# design.net
KiCad netlist of a schematic drawn in Altium Designer
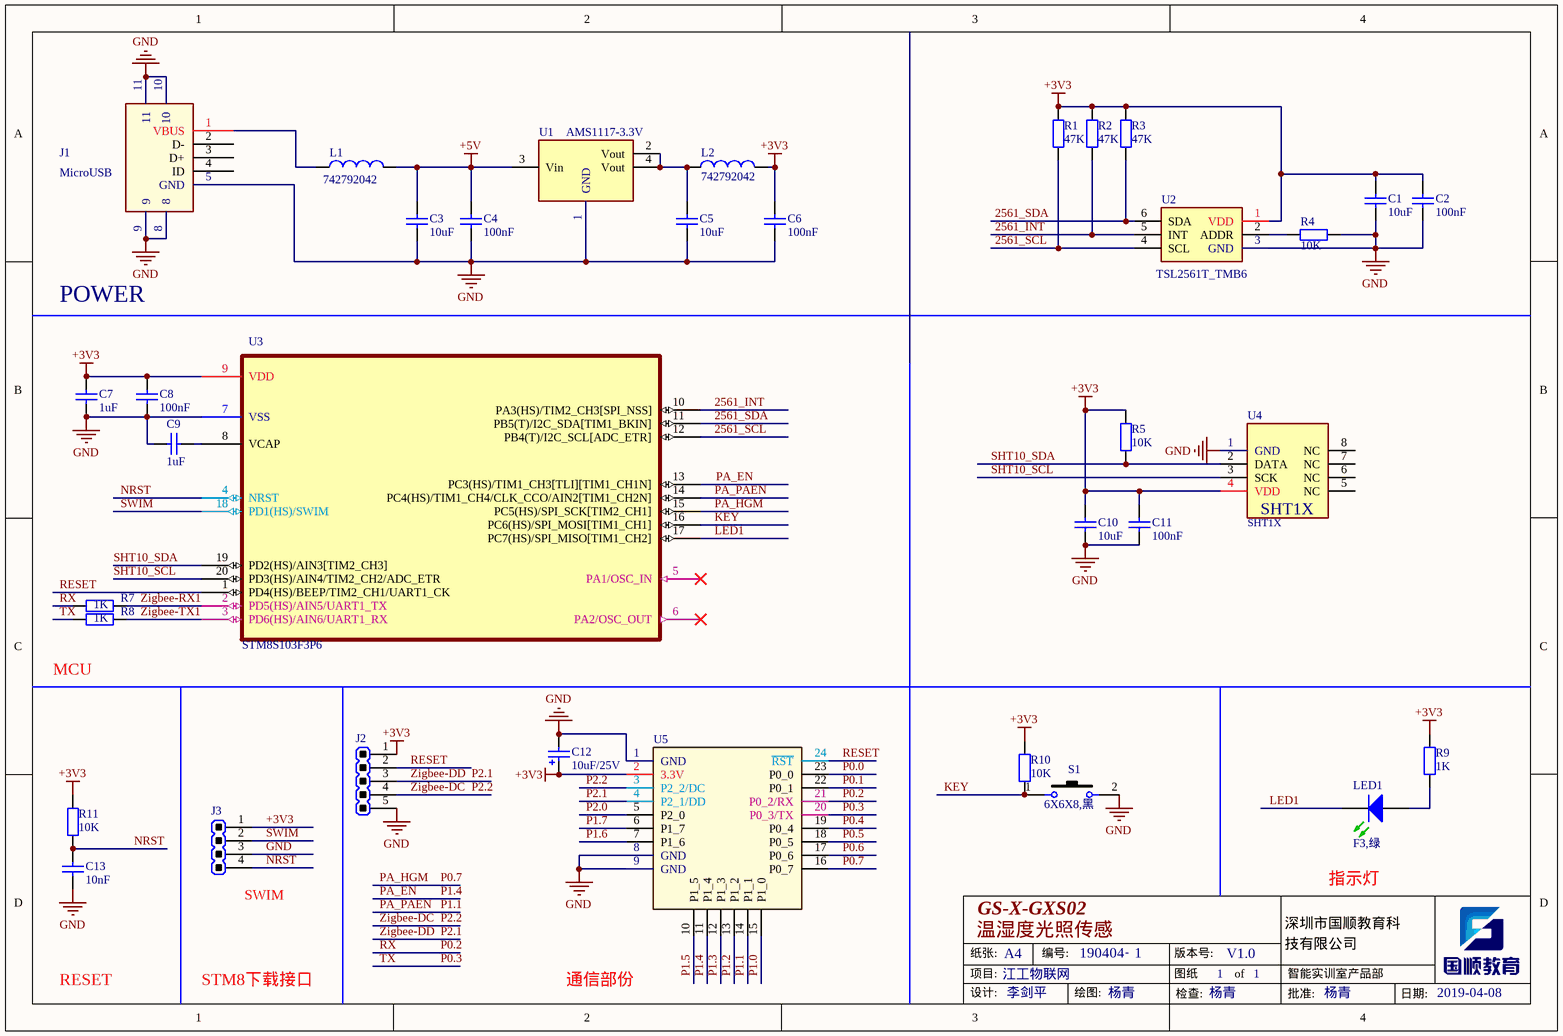
[diagram p0: 温湿度光照传感.SchDoc]

(export (version "E")
  (design (tool "Eeschema 10.0.6"))
  (components
    (comp (ref "C1")
      (value "10uF")
      (footprint "C0603")
      (description "Capacitor")
      (libsource (lib "贴片电容") (part "10uF_16V_0603"))
    )
    (comp (ref "C2")
      (value "100nF")
      (footprint "C0603")
      (description "Capacitor")
      (libsource (lib "贴片电容") (part "100nF_50V_0603"))
    )
    (comp (ref "C3")
      (value "10uF")
      (footprint "C0603")
      (description "Capacitor")
      (libsource (lib "贴片电容") (part "10uF_16V_0603"))
    )
    (comp (ref "C4")
      (value "100nF")
      (footprint "C0603")
      (description "Capacitor")
      (libsource (lib "贴片电容") (part "100nF_50V_0603"))
    )
    (comp (ref "C5")
      (value "10uF")
      (footprint "C0603")
      (description "Capacitor")
      (libsource (lib "贴片电容") (part "10uF_16V_0603"))
    )
    (comp (ref "C6")
      (value "100nF")
      (footprint "C0603")
      (description "Capacitor")
      (libsource (lib "贴片电容") (part "100nF_50V_0603"))
    )
    (comp (ref "C7")
      (value "1uF")
      (footprint "C0603")
      (description "Capacitor")
      (libsource (lib "贴片电容") (part "1uF_25V_X7R_0603"))
    )
    (comp (ref "C8")
      (value "100nF")
      (footprint "C0603")
      (description "Capacitor")
      (libsource (lib "贴片电容") (part "100nF_50V_0603"))
    )
    (comp (ref "C9")
      (value "1uF")
      (footprint "C0603")
      (description "Capacitor")
      (libsource (lib "贴片电容") (part "1uF_25V_X7R_0603"))
    )
    (comp (ref "C10")
      (value "10uF")
      (footprint "C0603")
      (description "Capacitor")
      (libsource (lib "贴片电容") (part "10uF_16V_0603"))
    )
    (comp (ref "C11")
      (value "100nF")
      (footprint "C0603")
      (description "Capacitor")
      (libsource (lib "贴片电容") (part "100nF_50V_0603"))
    )
    (comp (ref "C12")
      (value "10uF/25V")
      (footprint "TC3528X21B")
      (description "钽电容,10uF/25V-3528B")
      (libsource (lib "贴片电容") (part "CAPC-10uF/25V_3528B"))
    )
    (comp (ref "C13")
      (value "10nF")
      (footprint "C0603")
      (description "Capacitor")
      (libsource (lib "贴片电容") (part "10nF_16V_0603"))
    )
    (comp (ref "J1")
      (value "MicroUSB")
      (footprint "USB-F-Micro5P")
      (description "MicroUSB 母座")
      (libsource (lib "接口") (part "USB-F-Miro5P"))
    )
    (comp (ref "J2")
      (value "HDRM-2.54/11-1*5P-AK")
      (footprint "HDRM-2.54-1*5P-AK")
      (description "排针,直")
      (libsource (lib "接口") (part "HDRM-2.54/11-1*5P-AK"))
    )
    (comp (ref "J3")
      (value "HDRM-2.54/11-1*4P-AK")
      (footprint "HDRM-2.54-1*4P-AK")
      (description "排针,直")
      (libsource (lib "接口") (part "HDRM-2.54/11-1*4P-AK"))
    )
    (comp (ref "L1")
      (value "742792042")
      (footprint "L0805")
      (description "WE-CBF,600@100M,500Ohm,200mA,0805,742792042")
      (libsource (lib "电感") (part "BEAD-742792042_0805"))
    )
    (comp (ref "L2")
      (value "742792042")
      (footprint "L0805")
      (description "WE-CBF,600@100M,500Ohm,200mA,0805,742792042")
      (libsource (lib "电感") (part "BEAD-742792042_0805"))
    )
    (comp (ref "LED1")
      (value "F3,绿")
      (footprint "LED-F3-G-H")
      (description "F3,圆头,绿发绿")
      (libsource (lib "二极管") (part "LED-绿_F3"))
    )
    (comp (ref "R1")
      (value "47K")
      (footprint "R0603")
      (description "47K,±5%,0603")
      (libsource (lib "贴片电阻") (part "47K_5%_0603"))
    )
    (comp (ref "R2")
      (value "47K")
      (footprint "R0603")
      (description "47K,±5%,0603")
      (libsource (lib "贴片电阻") (part "47K_5%_0603"))
    )
    (comp (ref "R3")
      (value "47K")
      (footprint "R0603")
      (description "47K,±5%,0603")
      (libsource (lib "贴片电阻") (part "47K_5%_0603"))
    )
    (comp (ref "R4")
      (value "10K")
      (footprint "R0603")
      (description "10K,±5%,0603")
      (libsource (lib "") (part "10K_5%_0603_1"))
    )
    (comp (ref "R5")
      (value "10K")
      (footprint "R0603")
      (description "10K,±5%,0603")
      (libsource (lib "贴片电阻") (part "10K_5%_0603"))
    )
    (comp (ref "R7")
      (value "1K")
      (footprint "R0603")
      (description "1K,±5%,0603")
      (libsource (lib "贴片电阻") (part "1K_5%_0603"))
    )
    (comp (ref "R8")
      (value "1K")
      (footprint "R0603")
      (description "1K,±5%,0603")
      (libsource (lib "贴片电阻") (part "1K_5%_0603"))
    )
    (comp (ref "R9")
      (value "1K")
      (footprint "R0603")
      (description "1K,±5%,0603")
      (libsource (lib "") (part "1K_5%_0603_1"))
    )
    (comp (ref "R10")
      (value "10K")
      (footprint "R0603")
      (description "10K,±5%,0603")
      (libsource (lib "贴片电阻") (part "10K_5%_0603"))
    )
    (comp (ref "R11")
      (value "10K")
      (footprint "R0603")
      (description "10K,±5%,0603")
      (libsource (lib "贴片电阻") (part "10K_5%_0603"))
    )
    (comp (ref "S1")
      (value "6X6X8,黑")
      (footprint "SW-6.0X6.0X8.0-STAND-BK")
      (description "6X6X8,黑,插针,支架")
      (libsource (lib "按键开关") (part "SW-PB_6X6X8-STAND-BK"))
    )
    (comp (ref "U1")
      (value "AMS1117-3.3V")
      (footprint "SOT-223")
      (description "三端稳压器")
      (libsource (lib "IC") (part "AMS1117-3.3V_SOT223"))
    )
    (comp (ref "U2")
      (value "TSL2561T_TMB6")
      (footprint "TSL2561T")
      (description "光照传感器")
      (libsource (lib "传感器") (part "TSL2561T_TMB6"))
    )
    (comp (ref "U3")
      (value "STM8S103F3P6")
      (footprint "TSSOP20-0.65/4.4")
      (description "STM8 ARM-based 32-bit MCU with 8 Kbytes Flash, 20-pin TSSOP, Industrial Temperature")
      (libsource (lib "IC") (part "STM8S103F3P6_TSSOP20"))
    )
    (comp (ref "U4")
      (value "SHT1X")
      (footprint "SHT1X")
      (description "温湿度传感器")
      (libsource (lib "传感器") (part "SHT1X"))
    )
    (comp (ref "U5")
      (value "ZigBee_Z-0003")
      (footprint "Module_ZigBee_Z-0003")
      (description "zigbee模块接口")
      (libsource (lib "其他") (part "Module_ZigBee_Z-0003_1"))
    )
  )
  (nets
    (net (code "1") (name "+3V3") (class "Default")
      (node (ref "C1") (pin "1") (pinfunction "1_1") (pintype "passive"))
      (node (ref "C10") (pin "1") (pinfunction "1_1") (pintype "passive"))
      (node (ref "C11") (pin "1") (pinfunction "1_1") (pintype "passive"))
      (node (ref "C12") (pin "1") (pinfunction "1_1") (pintype "passive"))
      (node (ref "C2") (pin "1") (pinfunction "1_1") (pintype "passive"))
      (node (ref "C6") (pin "1") (pinfunction "1_1") (pintype "passive"))
      (node (ref "C7") (pin "1") (pinfunction "1_1") (pintype "passive"))
      (node (ref "C8") (pin "2") (pinfunction "2_2") (pintype "passive"))
      (node (ref "J2") (pin "1") (pinfunction "1_1") (pintype "passive"))
      (node (ref "J3") (pin "1") (pinfunction "1_1") (pintype "passive"))
      (node (ref "L2") (pin "2") (pinfunction "2_2") (pintype "passive"))
      (node (ref "R1") (pin "2") (pinfunction "2_2") (pintype "passive"))
      (node (ref "R10") (pin "2") (pinfunction "2_2") (pintype "passive"))
      (node (ref "R11") (pin "2") (pinfunction "2_2") (pintype "passive"))
      (node (ref "R2") (pin "2") (pinfunction "2_2") (pintype "passive"))
      (node (ref "R3") (pin "2") (pinfunction "2_2") (pintype "passive"))
      (node (ref "R5") (pin "2") (pinfunction "2_2") (pintype "passive"))
      (node (ref "R9") (pin "1") (pinfunction "1_1") (pintype "passive"))
      (node (ref "U2") (pin "1") (pinfunction "VDD_1") (pintype "passive"))
      (node (ref "U3") (pin "9") (pinfunction "VDD_9") (pintype "power_in"))
      (node (ref "U4") (pin "4") (pinfunction "VDD_4") (pintype "passive"))
      (node (ref "U5") (pin "2") (pinfunction "3.3V_2") (pintype "passive"))
    )
    (net (code "2") (name "+5V") (class "Default")
      (node (ref "C3") (pin "1") (pinfunction "1_1") (pintype "passive"))
      (node (ref "C4") (pin "1") (pinfunction "1_1") (pintype "passive"))
      (node (ref "L1") (pin "2") (pinfunction "2_2") (pintype "passive"))
      (node (ref "U1") (pin "3") (pinfunction "Vin_3") (pintype "passive"))
    )
    (net (code "3") (name "/2561_INT") (class "Default")
      (node (ref "R2") (pin "1") (pinfunction "1_1") (pintype "passive"))
      (node (ref "U2") (pin "5") (pinfunction "INT_5") (pintype "passive"))
      (node (ref "U3") (pin "10") (pinfunction "PA3(HS)/TIM2_CH3[SPI_NSS]_10") (pintype "bidirectional"))
    )
    (net (code "4") (name "/2561_SCL") (class "Default")
      (node (ref "R1") (pin "1") (pinfunction "1_1") (pintype "passive"))
      (node (ref "U2") (pin "4") (pinfunction "SCL_4") (pintype "passive"))
      (node (ref "U3") (pin "12") (pinfunction "PB4(T)/I2C_SCL[ADC_ETR]_12") (pintype "bidirectional"))
    )
    (net (code "5") (name "/2561_SDA") (class "Default")
      (node (ref "R3") (pin "1") (pinfunction "1_1") (pintype "passive"))
      (node (ref "U2") (pin "6") (pinfunction "SDA_6") (pintype "passive"))
      (node (ref "U3") (pin "11") (pinfunction "PB5(T)/I2C_SDA[TIM1_BKIN]_11") (pintype "bidirectional"))
    )
    (net (code "6") (name "/KEY") (class "Default")
      (node (ref "R10") (pin "1") (pinfunction "1_1") (pintype "passive"))
      (node (ref "S1") (pin "1") (pinfunction "1_1") (pintype "passive"))
      (node (ref "U3") (pin "16") (pinfunction "PC6(HS)/SPI_MOSI[TIM1_CH1]_16") (pintype "bidirectional"))
    )
    (net (code "7") (name "/LED1") (class "Default")
      (node (ref "LED1") (pin "2") (pinfunction "K_2") (pintype "passive"))
      (node (ref "U3") (pin "17") (pinfunction "PC7(HS)/SPI_MISO[TIM1_CH2]_17") (pintype "bidirectional"))
    )
    (net (code "8") (name "/NRST") (class "Default")
      (node (ref "C13") (pin "2") (pinfunction "2_2") (pintype "passive"))
      (node (ref "J3") (pin "4") (pinfunction "4_4") (pintype "passive"))
      (node (ref "R11") (pin "1") (pinfunction "1_1") (pintype "passive"))
      (node (ref "U3") (pin "4") (pinfunction "NRST_4") (pintype "bidirectional"))
    )
    (net (code "9") (name "/P0.0") (class "Default")
      (node (ref "U5") (pin "23") (pinfunction "P0_0_23") (pintype "passive"))
    )
    (net (code "10") (name "/P0.1") (class "Default")
      (node (ref "U5") (pin "22") (pinfunction "P0_1_22") (pintype "passive"))
    )
    (net (code "11") (name "/P0.2") (class "Default")
      (node (ref "R7") (pin "1") (pinfunction "1_1") (pintype "passive"))
      (node (ref "U5") (pin "21") (pinfunction "P0_2/RX_21") (pintype "passive"))
    )
    (net (code "12") (name "/P0.3") (class "Default")
      (node (ref "R8") (pin "1") (pinfunction "1_1") (pintype "passive"))
      (node (ref "U5") (pin "20") (pinfunction "P0_3/TX_20") (pintype "passive"))
    )
    (net (code "13") (name "/P0.4") (class "Default")
      (node (ref "U5") (pin "19") (pinfunction "P0_4_19") (pintype "passive"))
    )
    (net (code "14") (name "/P0.5") (class "Default")
      (node (ref "U5") (pin "18") (pinfunction "P0_5_18") (pintype "passive"))
    )
    (net (code "15") (name "/P0.6") (class "Default")
      (node (ref "U5") (pin "17") (pinfunction "P0_6_17") (pintype "passive"))
    )
    (net (code "16") (name "/P0.7") (class "Default")
      (node (ref "U3") (pin "15") (pinfunction "PC5(HS)/SPI_SCK[TIM2_CH1]_15") (pintype "bidirectional"))
      (node (ref "U5") (pin "16") (pinfunction "P0_7_16") (pintype "passive"))
    )
    (net (code "17") (name "/P1.0") (class "Default")
      (node (ref "U5") (pin "15") (pinfunction "P1_0_15") (pintype "passive"))
    )
    (net (code "18") (name "/P1.1") (class "Default")
      (node (ref "U3") (pin "14") (pinfunction "PC4(HS)/TIM1_CH4/CLK_CCO/AIN2[TIM1_CH2N]_14") (pintype "bidirectional"))
      (node (ref "U5") (pin "14") (pinfunction "P1_1_14") (pintype "passive"))
    )
    (net (code "19") (name "/P1.2") (class "Default")
      (node (ref "U5") (pin "13") (pinfunction "P1_2_13") (pintype "passive"))
    )
    (net (code "20") (name "/P1.3") (class "Default")
      (node (ref "U5") (pin "12") (pinfunction "P1_3_12") (pintype "passive"))
    )
    (net (code "21") (name "/P1.4") (class "Default")
      (node (ref "U3") (pin "13") (pinfunction "PC3(HS)/TIM1_CH3[TLI][TIM1_CH1N]_13") (pintype "bidirectional"))
      (node (ref "U5") (pin "11") (pinfunction "P1_4_11") (pintype "passive"))
    )
    (net (code "22") (name "/P1.5") (class "Default")
      (node (ref "U5") (pin "10") (pinfunction "P1_5_10") (pintype "passive"))
    )
    (net (code "23") (name "/P1.6") (class "Default")
      (node (ref "U5") (pin "7") (pinfunction "P1_6_7") (pintype "passive"))
    )
    (net (code "24") (name "/P1.7") (class "Default")
      (node (ref "U5") (pin "6") (pinfunction "P1_7_6") (pintype "passive"))
    )
    (net (code "25") (name "/P2.0") (class "Default")
      (node (ref "U5") (pin "5") (pinfunction "P2_0_5") (pintype "passive"))
    )
    (net (code "26") (name "/P2.1") (class "Default")
      (node (ref "J2") (pin "3") (pinfunction "3_3") (pintype "passive"))
      (node (ref "U5") (pin "4") (pinfunction "P2_1/DD_4") (pintype "passive"))
    )
    (net (code "27") (name "/P2.2") (class "Default")
      (node (ref "J2") (pin "4") (pinfunction "4_4") (pintype "passive"))
      (node (ref "U5") (pin "3") (pinfunction "P2_2/DC_3") (pintype "passive"))
    )
    (net (code "28") (name "/RESET") (class "Default")
      (node (ref "J2") (pin "2") (pinfunction "2_2") (pintype "passive"))
      (node (ref "U3") (pin "1") (pinfunction "PD4(HS)/BEEP/TIM2_CH1/UART1_CK_1") (pintype "bidirectional"))
      (node (ref "U5") (pin "24") (pinfunction "~{RST}_24") (pintype "passive"))
    )
    (net (code "29") (name "/SHT10_SCL") (class "Default")
      (node (ref "U3") (pin "20") (pinfunction "PD3(HS)/AIN4/TIM2_CH2/ADC_ETR_20") (pintype "bidirectional"))
      (node (ref "U4") (pin "3") (pinfunction "SCK_3") (pintype "passive"))
    )
    (net (code "30") (name "/SHT10_SDA") (class "Default")
      (node (ref "R5") (pin "1") (pinfunction "1_1") (pintype "passive"))
      (node (ref "U3") (pin "19") (pinfunction "PD2(HS)/AIN3[TIM2_CH3]_19") (pintype "bidirectional"))
      (node (ref "U4") (pin "2") (pinfunction "DATA_2") (pintype "passive"))
    )
    (net (code "31") (name "/SWIM") (class "Default")
      (node (ref "J3") (pin "2") (pinfunction "2_2") (pintype "passive"))
      (node (ref "U3") (pin "18") (pinfunction "PD1(HS)/SWIM_18") (pintype "bidirectional"))
    )
    (net (code "32") (name "/Zigbee-RX1") (class "Default")
      (node (ref "R7") (pin "2") (pinfunction "2_2") (pintype "passive"))
      (node (ref "U3") (pin "2") (pinfunction "PD5(HS)/AIN5/UART1_TX_2") (pintype "bidirectional"))
    )
    (net (code "33") (name "/Zigbee-TX1") (class "Default")
      (node (ref "R8") (pin "2") (pinfunction "2_2") (pintype "passive"))
      (node (ref "U3") (pin "3") (pinfunction "PD6(HS)/AIN6/UART1_RX_3") (pintype "bidirectional"))
    )
    (net (code "34") (name "GND") (class "Default")
      (node (ref "C1") (pin "2") (pinfunction "2_2") (pintype "passive"))
      (node (ref "C10") (pin "2") (pinfunction "2_2") (pintype "passive"))
      (node (ref "C11") (pin "2") (pinfunction "2_2") (pintype "passive"))
      (node (ref "C12") (pin "2") (pinfunction "2_2") (pintype "passive"))
      (node (ref "C13") (pin "1") (pinfunction "1_1") (pintype "passive"))
      (node (ref "C2") (pin "2") (pinfunction "2_2") (pintype "passive"))
      (node (ref "C3") (pin "2") (pinfunction "2_2") (pintype "passive"))
      (node (ref "C4") (pin "2") (pinfunction "2_2") (pintype "passive"))
      (node (ref "C5") (pin "2") (pinfunction "2_2") (pintype "passive"))
      (node (ref "C6") (pin "2") (pinfunction "2_2") (pintype "passive"))
      (node (ref "C7") (pin "2") (pinfunction "2_2") (pintype "passive"))
      (node (ref "C8") (pin "1") (pinfunction "1_1") (pintype "passive"))
      (node (ref "C9") (pin "2") (pinfunction "2_2") (pintype "passive"))
      (node (ref "J1") (pin "10") (pinfunction "10_10") (pintype "passive"))
      (node (ref "J1") (pin "11") (pinfunction "11_11") (pintype "passive"))
      (node (ref "J1") (pin "5") (pinfunction "GND_5") (pintype "passive"))
      (node (ref "J1") (pin "8") (pinfunction "8_8") (pintype "passive"))
      (node (ref "J1") (pin "9") (pinfunction "9_9") (pintype "passive"))
      (node (ref "J2") (pin "5") (pinfunction "5_5") (pintype "passive"))
      (node (ref "J3") (pin "3") (pinfunction "3_3") (pintype "passive"))
      (node (ref "R4") (pin "1") (pinfunction "1_1") (pintype "passive"))
      (node (ref "S1") (pin "2") (pinfunction "2_2") (pintype "passive"))
      (node (ref "U1") (pin "1") (pinfunction "GND_1") (pintype "passive"))
      (node (ref "U2") (pin "3") (pinfunction "GND_3") (pintype "passive"))
      (node (ref "U3") (pin "7") (pinfunction "VSS_7") (pintype "power_in"))
      (node (ref "U4") (pin "1") (pinfunction "GND_1") (pintype "passive"))
      (node (ref "U5") (pin "1") (pinfunction "GND_1") (pintype "passive"))
      (node (ref "U5") (pin "8") (pinfunction "GND_8") (pintype "passive"))
      (node (ref "U5") (pin "9") (pinfunction "GND_9") (pintype "passive"))
    )
    (net (code "35") (name "Net-(C5-Pad1)") (class "Default")
      (node (ref "C5") (pin "1") (pinfunction "1_1") (pintype "passive"))
      (node (ref "L2") (pin "1") (pinfunction "1_1") (pintype "passive"))
      (node (ref "U1") (pin "2") (pinfunction "Vout_2") (pintype "passive"))
      (node (ref "U1") (pin "4") (pinfunction "Vout_4") (pintype "passive"))
    )
    (net (code "36") (name "Net-(J1-VBUS)") (class "Default")
      (node (ref "J1") (pin "1") (pinfunction "VBUS_1") (pintype "passive"))
      (node (ref "L1") (pin "1") (pinfunction "1_1") (pintype "passive"))
    )
    (net (code "37") (name "Net-(LED1-A)") (class "Default")
      (node (ref "LED1") (pin "1") (pinfunction "A_1") (pintype "passive"))
      (node (ref "R9") (pin "2") (pinfunction "2_2") (pintype "passive"))
    )
    (net (code "38") (name "Net-(U2-ADDR)") (class "Default")
      (node (ref "R4") (pin "2") (pinfunction "2_2") (pintype "passive"))
      (node (ref "U2") (pin "2") (pinfunction "ADDR_2") (pintype "passive"))
    )
    (net (code "39") (name "Net-(U3-VCAP)") (class "Default")
      (node (ref "C9") (pin "1") (pinfunction "1_1") (pintype "passive"))
      (node (ref "U3") (pin "8") (pinfunction "VCAP_8") (pintype "passive"))
    )
    (net (code "40") (name "unconnected-(J1-D+-Pad3)") (class "Default")
      (node (ref "J1") (pin "3") (pinfunction "D+_3") (pintype "passive"))
    )
    (net (code "41") (name "unconnected-(J1-D--Pad2)") (class "Default")
      (node (ref "J1") (pin "2") (pinfunction "D-_2") (pintype "passive"))
    )
    (net (code "42") (name "unconnected-(J1-ID-Pad4)") (class "Default")
      (node (ref "J1") (pin "4") (pinfunction "ID_4") (pintype "passive"))
    )
    (net (code "43") (name "unconnected-(U3-PA1{slash}OSC_IN-Pad5)") (class "Default")
      (node (ref "U3") (pin "5") (pinfunction "PA1/OSC_IN_5") (pintype "input+no_connect"))
    )
    (net (code "44") (name "unconnected-(U3-PA2{slash}OSC_OUT-Pad6)") (class "Default")
      (node (ref "U3") (pin "6") (pinfunction "PA2/OSC_OUT_6") (pintype "output+no_connect"))
    )
    (net (code "45") (name "unconnected-(U4-NC-Pad5)") (class "Default")
      (node (ref "U4") (pin "5") (pinfunction "NC_5") (pintype "passive"))
    )
    (net (code "46") (name "unconnected-(U4-NC-Pad6)") (class "Default")
      (node (ref "U4") (pin "6") (pinfunction "NC_6") (pintype "passive"))
    )
    (net (code "47") (name "unconnected-(U4-NC-Pad7)") (class "Default")
      (node (ref "U4") (pin "7") (pinfunction "NC_7") (pintype "passive"))
    )
    (net (code "48") (name "unconnected-(U4-NC-Pad8)") (class "Default")
      (node (ref "U4") (pin "8") (pinfunction "NC_8") (pintype "passive"))
    )
  )
)
